# -46342_21-004_3_7.net
KiCad netlist of a schematic drawn in Altium Designer
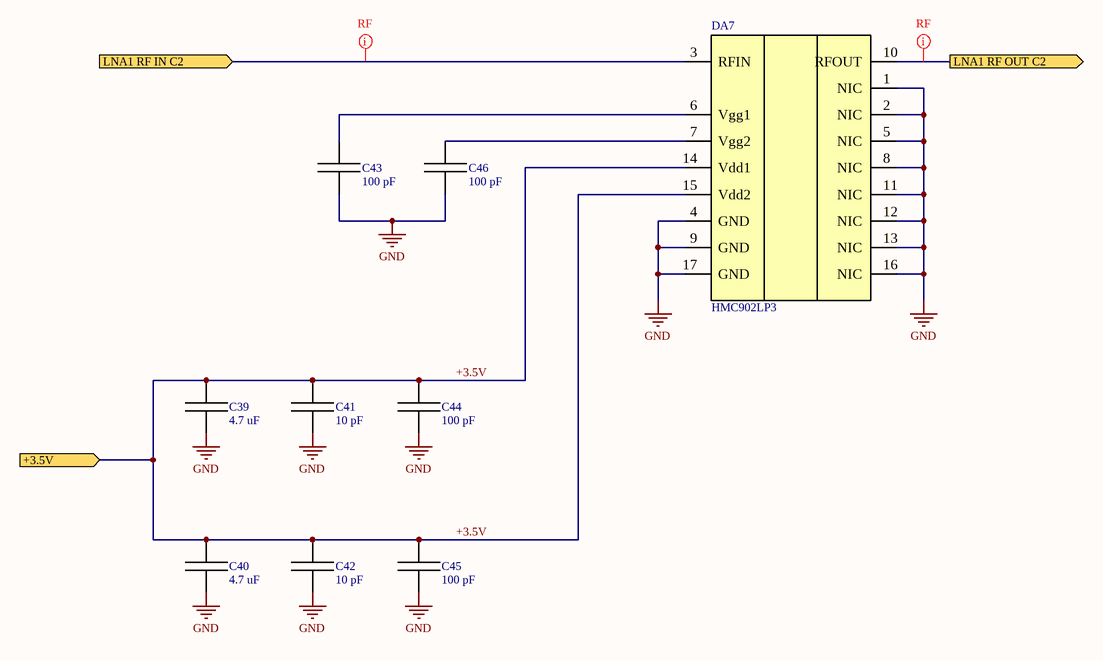
[diagram p0: МПСУ-46342.21-004 Э3 Лист7.SchDoc]

(export (version "E")
  (design (tool "Eeschema 10.0.6"))
  (components
    (comp (ref "C39")
      (value "4.7 uF")
      (footprint "CAPC160X80X90L30N")
      (description "Capacitor, generic")
      (fields (field (name "TOLERANCE") "5 %"))
      (libsource (lib "StudentsLibrary") (part "Capacitor"))
    )
    (comp (ref "C40")
      (value "4.7 uF")
      (footprint "CAPC160X80X90L30N")
      (description "Capacitor, generic")
      (fields (field (name "TOLERANCE") "5 %"))
      (libsource (lib "StudentsLibrary") (part "Capacitor"))
    )
    (comp (ref "C41")
      (value "10 pF")
      (footprint "CAPC100X50X55L20N")
      (description "Capacitor, generic")
      (fields (field (name "TOLERANCE") "5 %"))
      (libsource (lib "StudentsLibrary") (part "Capacitor"))
    )
    (comp (ref "C42")
      (value "10 pF")
      (footprint "CAPC100X50X55L20N")
      (description "Capacitor, generic")
      (fields (field (name "TOLERANCE") "5 %"))
      (libsource (lib "StudentsLibrary") (part "Capacitor"))
    )
    (comp (ref "C43")
      (value "100 pF")
      (footprint "CAPC100X50X55L20N")
      (description "Capacitor, generic")
      (fields (field (name "TOLERANCE") "5 %"))
      (libsource (lib "StudentsLibrary") (part "Capacitor"))
    )
    (comp (ref "C44")
      (value "100 pF")
      (footprint "CAPC100X50X55L20N")
      (description "Capacitor, generic")
      (fields (field (name "TOLERANCE") "5 %"))
      (libsource (lib "StudentsLibrary") (part "Capacitor"))
    )
    (comp (ref "C45")
      (value "100 pF")
      (footprint "CAPC100X50X55L20N")
      (description "Capacitor, generic")
      (fields (field (name "TOLERANCE") "5 %"))
      (libsource (lib "StudentsLibrary") (part "Capacitor"))
    )
    (comp (ref "C46")
      (value "100 pF")
      (footprint "CAPC100X50X55L20N")
      (description "Capacitor, generic")
      (fields (field (name "TOLERANCE") "5 %"))
      (libsource (lib "StudentsLibrary") (part "Capacitor"))
    )
    (comp (ref "DA7")
      (value "HMC902LP3")
      (footprint "QFN17P50_300X300X90L40X25T170N")
      (description "GaAs, pHEMT, MMIC, Low Noise Amplifier, 5 GHz to 11 GHz")
      (fields (field (name "MANUFACTURER") "Analog Devices"))
      (libsource (lib "receiver") (part "HMC902LP3"))
    )
  )
  (nets
    (net (code "1") (name "/+3.5V") (class "Default")
      (node (ref "C39") (pin "2") (pinfunction "2_2") (pintype "passive"))
      (node (ref "C40") (pin "2") (pinfunction "2_2") (pintype "passive"))
      (node (ref "C41") (pin "2") (pinfunction "2_2") (pintype "passive"))
      (node (ref "C42") (pin "2") (pinfunction "2_2") (pintype "passive"))
      (node (ref "C44") (pin "2") (pinfunction "2_2") (pintype "passive"))
      (node (ref "C45") (pin "2") (pinfunction "2_2") (pintype "passive"))
      (node (ref "DA7") (pin "14") (pinfunction "Vdd1_14") (pintype "passive"))
      (node (ref "DA7") (pin "15") (pinfunction "Vdd2_15") (pintype "passive"))
    )
    (net (code "2") (name "/LNA1 RF IN C2") (class "Default")
      (node (ref "DA7") (pin "3") (pinfunction "RFIN_3") (pintype "passive"))
    )
    (net (code "3") (name "/LNA1 RF OUT C2") (class "Default")
      (node (ref "DA7") (pin "10") (pinfunction "RFOUT_10") (pintype "passive"))
    )
    (net (code "4") (name "GND") (class "Default")
      (node (ref "C39") (pin "1") (pinfunction "1_1") (pintype "passive"))
      (node (ref "C40") (pin "1") (pinfunction "1_1") (pintype "passive"))
      (node (ref "C41") (pin "1") (pinfunction "1_1") (pintype "passive"))
      (node (ref "C42") (pin "1") (pinfunction "1_1") (pintype "passive"))
      (node (ref "C43") (pin "1") (pinfunction "1_1") (pintype "passive"))
      (node (ref "C44") (pin "1") (pinfunction "1_1") (pintype "passive"))
      (node (ref "C45") (pin "1") (pinfunction "1_1") (pintype "passive"))
      (node (ref "C46") (pin "1") (pinfunction "1_1") (pintype "passive"))
      (node (ref "DA7") (pin "1") (pinfunction "NIC_1") (pintype "passive"))
      (node (ref "DA7") (pin "11") (pinfunction "NIC_11") (pintype "passive"))
      (node (ref "DA7") (pin "12") (pinfunction "NIC_12") (pintype "passive"))
      (node (ref "DA7") (pin "13") (pinfunction "NIC_13") (pintype "passive"))
      (node (ref "DA7") (pin "16") (pinfunction "NIC_16") (pintype "passive"))
      (node (ref "DA7") (pin "17") (pinfunction "GND_17") (pintype "passive"))
      (node (ref "DA7") (pin "2") (pinfunction "NIC_2") (pintype "passive"))
      (node (ref "DA7") (pin "4") (pinfunction "GND_4") (pintype "passive"))
      (node (ref "DA7") (pin "5") (pinfunction "NIC_5") (pintype "passive"))
      (node (ref "DA7") (pin "8") (pinfunction "NIC_8") (pintype "passive"))
      (node (ref "DA7") (pin "9") (pinfunction "GND_9") (pintype "passive"))
    )
    (net (code "5") (name "Net-(DA7-Vgg1)") (class "Default")
      (node (ref "C43") (pin "2") (pinfunction "2_2") (pintype "passive"))
      (node (ref "DA7") (pin "6") (pinfunction "Vgg1_6") (pintype "passive"))
    )
    (net (code "6") (name "Net-(DA7-Vgg2)") (class "Default")
      (node (ref "C46") (pin "2") (pinfunction "2_2") (pintype "passive"))
      (node (ref "DA7") (pin "7") (pinfunction "Vgg2_7") (pintype "passive"))
    )
  )
)
